# EBAZ4205__RGB_RX.net
KiCad netlist of a schematic drawn in Altium Designer
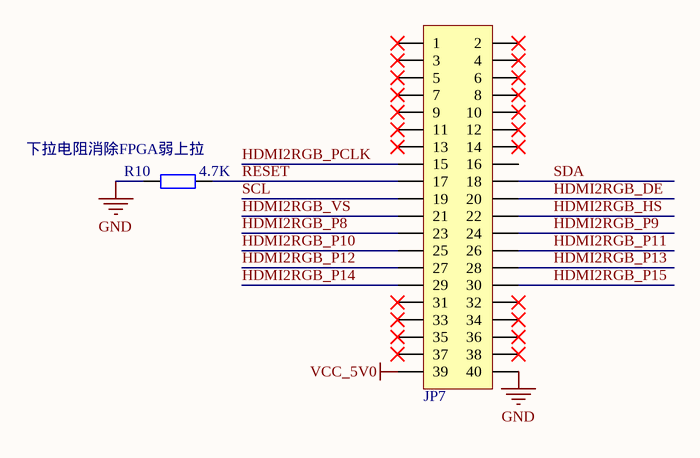
[diagram p0: EBAZ4205扩展_RGB_RX.SchDoc]

(export (version "E")
  (design (tool "Eeschema 10.0.6"))
  (components
    (comp (ref "JP7")
      (value "Header 2X11")
      (footprint "PHD2.0-LI-2x20P")
      (description "20*2P接插件")
      (libsource (lib "5.4 - 接插件-脚距2.0") (part "Header 20X2"))
    )
    (comp (ref "R10")
      (value "4.7K")
      (footprint "R0402_L")
      (description "贴片电阻")
      (fields (field (name "4.作者声明") "旨为整合最全库集,欢迎转载,禁止商用！-冰凌猫") (field (name "1.库作者") "冰凌猫"))
      (libsource (lib "0.1 - 电阻-电容-电感-磁珠-电位器") (part "R"))
    )
  )
  (nets
    (net (code "1") (name "/HDMI2RGB_DE") (class "Default")
      (node (ref "JP7") (pin "20") (pinfunction "20_20") (pintype "passive"))
    )
    (net (code "2") (name "/HDMI2RGB_HS") (class "Default")
      (node (ref "JP7") (pin "22") (pinfunction "22_22") (pintype "passive"))
    )
    (net (code "3") (name "/HDMI2RGB_P8") (class "Default")
      (node (ref "JP7") (pin "23") (pinfunction "23_23") (pintype "passive"))
    )
    (net (code "4") (name "/HDMI2RGB_P9") (class "Default")
      (node (ref "JP7") (pin "24") (pinfunction "24_24") (pintype "passive"))
    )
    (net (code "5") (name "/HDMI2RGB_P10") (class "Default")
      (node (ref "JP7") (pin "25") (pinfunction "25_25") (pintype "passive"))
    )
    (net (code "6") (name "/HDMI2RGB_P11") (class "Default")
      (node (ref "JP7") (pin "26") (pinfunction "26_26") (pintype "passive"))
    )
    (net (code "7") (name "/HDMI2RGB_P12") (class "Default")
      (node (ref "JP7") (pin "27") (pinfunction "27_27") (pintype "passive"))
    )
    (net (code "8") (name "/HDMI2RGB_P13") (class "Default")
      (node (ref "JP7") (pin "28") (pinfunction "28_28") (pintype "passive"))
    )
    (net (code "9") (name "/HDMI2RGB_P14") (class "Default")
      (node (ref "JP7") (pin "29") (pinfunction "29_29") (pintype "passive"))
    )
    (net (code "10") (name "/HDMI2RGB_P15") (class "Default")
      (node (ref "JP7") (pin "30") (pinfunction "30_30") (pintype "passive"))
    )
    (net (code "11") (name "/HDMI2RGB_PCLK") (class "Default")
      (node (ref "JP7") (pin "15") (pinfunction "15_15") (pintype "passive"))
    )
    (net (code "12") (name "/HDMI2RGB_VS") (class "Default")
      (node (ref "JP7") (pin "21") (pinfunction "21_21") (pintype "passive"))
    )
    (net (code "13") (name "/RESET") (class "Default")
      (node (ref "JP7") (pin "17") (pinfunction "17_17") (pintype "passive"))
      (node (ref "R10") (pin "2") (pinfunction "2_2") (pintype "passive"))
    )
    (net (code "14") (name "/SCL") (class "Default")
      (node (ref "JP7") (pin "19") (pinfunction "19_19") (pintype "passive"))
    )
    (net (code "15") (name "/SDA") (class "Default")
      (node (ref "JP7") (pin "18") (pinfunction "18_18") (pintype "passive"))
    )
    (net (code "16") (name "GND") (class "Default")
      (node (ref "JP7") (pin "40") (pinfunction "40_40") (pintype "passive"))
      (node (ref "R10") (pin "1") (pinfunction "1_1") (pintype "passive"))
    )
    (net (code "17") (name "VCC_5V0") (class "Default")
      (node (ref "JP7") (pin "39") (pinfunction "39_39") (pintype "passive"))
    )
    (net (code "18") (name "unconnected-(JP7-Pad1)") (class "Default")
      (node (ref "JP7") (pin "1") (pinfunction "1_1") (pintype "passive+no_connect"))
    )
    (net (code "19") (name "unconnected-(JP7-Pad2)") (class "Default")
      (node (ref "JP7") (pin "2") (pinfunction "2_2") (pintype "passive+no_connect"))
    )
    (net (code "20") (name "unconnected-(JP7-Pad3)") (class "Default")
      (node (ref "JP7") (pin "3") (pinfunction "3_3") (pintype "passive+no_connect"))
    )
    (net (code "21") (name "unconnected-(JP7-Pad4)") (class "Default")
      (node (ref "JP7") (pin "4") (pinfunction "4_4") (pintype "passive+no_connect"))
    )
    (net (code "22") (name "unconnected-(JP7-Pad5)") (class "Default")
      (node (ref "JP7") (pin "5") (pinfunction "5_5") (pintype "passive+no_connect"))
    )
    (net (code "23") (name "unconnected-(JP7-Pad6)") (class "Default")
      (node (ref "JP7") (pin "6") (pinfunction "6_6") (pintype "passive+no_connect"))
    )
    (net (code "24") (name "unconnected-(JP7-Pad7)") (class "Default")
      (node (ref "JP7") (pin "7") (pinfunction "7_7") (pintype "passive+no_connect"))
    )
    (net (code "25") (name "unconnected-(JP7-Pad8)") (class "Default")
      (node (ref "JP7") (pin "8") (pinfunction "8_8") (pintype "passive+no_connect"))
    )
    (net (code "26") (name "unconnected-(JP7-Pad9)") (class "Default")
      (node (ref "JP7") (pin "9") (pinfunction "9_9") (pintype "passive+no_connect"))
    )
    (net (code "27") (name "unconnected-(JP7-Pad10)") (class "Default")
      (node (ref "JP7") (pin "10") (pinfunction "10_10") (pintype "passive+no_connect"))
    )
    (net (code "28") (name "unconnected-(JP7-Pad11)") (class "Default")
      (node (ref "JP7") (pin "11") (pinfunction "11_11") (pintype "passive+no_connect"))
    )
    (net (code "29") (name "unconnected-(JP7-Pad12)") (class "Default")
      (node (ref "JP7") (pin "12") (pinfunction "12_12") (pintype "passive+no_connect"))
    )
    (net (code "30") (name "unconnected-(JP7-Pad13)") (class "Default")
      (node (ref "JP7") (pin "13") (pinfunction "13_13") (pintype "passive+no_connect"))
    )
    (net (code "31") (name "unconnected-(JP7-Pad14)") (class "Default")
      (node (ref "JP7") (pin "14") (pinfunction "14_14") (pintype "passive+no_connect"))
    )
    (net (code "32") (name "unconnected-(JP7-Pad16)") (class "Default")
      (node (ref "JP7") (pin "16") (pinfunction "16_16") (pintype "passive"))
    )
    (net (code "33") (name "unconnected-(JP7-Pad31)") (class "Default")
      (node (ref "JP7") (pin "31") (pinfunction "31_31") (pintype "passive+no_connect"))
    )
    (net (code "34") (name "unconnected-(JP7-Pad32)") (class "Default")
      (node (ref "JP7") (pin "32") (pinfunction "32_32") (pintype "passive+no_connect"))
    )
    (net (code "35") (name "unconnected-(JP7-Pad33)") (class "Default")
      (node (ref "JP7") (pin "33") (pinfunction "33_33") (pintype "passive+no_connect"))
    )
    (net (code "36") (name "unconnected-(JP7-Pad34)") (class "Default")
      (node (ref "JP7") (pin "34") (pinfunction "34_34") (pintype "passive+no_connect"))
    )
    (net (code "37") (name "unconnected-(JP7-Pad35)") (class "Default")
      (node (ref "JP7") (pin "35") (pinfunction "35_35") (pintype "passive+no_connect"))
    )
    (net (code "38") (name "unconnected-(JP7-Pad36)") (class "Default")
      (node (ref "JP7") (pin "36") (pinfunction "36_36") (pintype "passive+no_connect"))
    )
    (net (code "39") (name "unconnected-(JP7-Pad37)") (class "Default")
      (node (ref "JP7") (pin "37") (pinfunction "37_37") (pintype "passive+no_connect"))
    )
    (net (code "40") (name "unconnected-(JP7-Pad38)") (class "Default")
      (node (ref "JP7") (pin "38") (pinfunction "38_38") (pintype "passive+no_connect"))
    )
  )
)
